# main.net
KiCad netlist of a schematic drawn in EAGLE
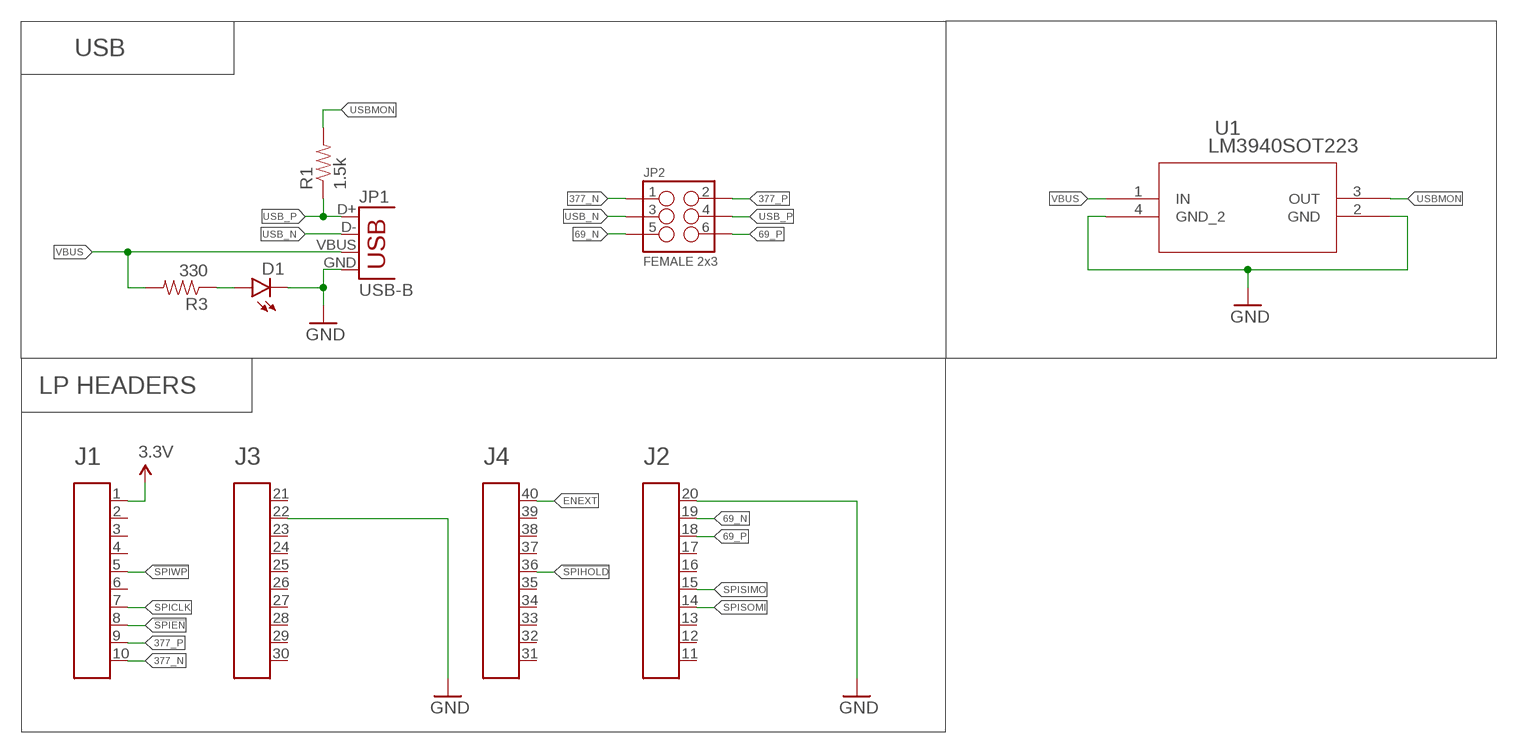
[diagram p0: schematic, sheet 1]

(export (version "E")
  (design (tool "Eeschema 10.0.6"))
  (components
    (comp (ref "A1")
      (value "HEADER4X10-BOOSTERPACK")
      (footprint "eagle-import:4X10-BOOSTERPACK")
      (libsource (lib "eagle-import") (part "HEADER4X10-BOOSTERPACK"))
    )
    (comp (ref "D1")
      (value "LED3MM")
      (footprint "eagle-import:LED3MM")
      (libsource (lib "eagle-import") (part "LED3MM"))
    )
    (comp (ref "JP1")
      (value "USB-B")
      (footprint "eagle-import:USB-B-PTH")
      (libsource (lib "eagle-import") (part "USBPTH"))
    )
    (comp (ref "JP2")
      (value "FEMALE 2x3")
      (footprint "eagle-import:2X3")
      (libsource (lib "eagle-import") (part "M03X2FEMALE"))
    )
    (comp (ref "R1")
      (value "1.5k")
      (footprint "eagle-import:AXIAL-0.3")
      (libsource (lib "eagle-import") (part "1KOHM-1/4W-5%(PTH)"))
    )
    (comp (ref "R3")
      (value "330")
      (footprint "eagle-import:AXIAL-0.3")
      (libsource (lib "eagle-import") (part "1KOHM-1/4W-5%(PTH)"))
    )
    (comp (ref "U1")
      (value "LM3940SOT223")
      (footprint "eagle-import:DCY")
      (libsource (lib "eagle-import") (part "LM3940SOT223"))
    )
  )
  (nets
    (net (code "1") (name "/~{SPIEN}") (class "Default")
      (node (ref "A1") (pin "8") (pinfunction "P$8_8") (pintype "bidirectional"))
    )
    (net (code "2") (name "/~{SPIHOLD}") (class "Default")
      (node (ref "A1") (pin "36") (pinfunction "P$36_36") (pintype "bidirectional"))
    )
    (net (code "3") (name "/~{SPIWP}") (class "Default")
      (node (ref "A1") (pin "5") (pinfunction "P$5_5") (pintype "bidirectional"))
    )
    (net (code "4") (name "3.3V") (class "Default")
      (node (ref "A1") (pin "1") (pinfunction "P$1_1") (pintype "bidirectional"))
    )
    (net (code "5") (name "69_N") (class "Default")
      (node (ref "A1") (pin "19") (pinfunction "P$19_19") (pintype "bidirectional"))
      (node (ref "JP2") (pin "5") (pinfunction "5_5") (pintype "bidirectional"))
    )
    (net (code "6") (name "69_P") (class "Default")
      (node (ref "A1") (pin "18") (pinfunction "P$18_18") (pintype "bidirectional"))
      (node (ref "JP2") (pin "6") (pinfunction "6_6") (pintype "bidirectional"))
    )
    (net (code "7") (name "377_N") (class "Default")
      (node (ref "A1") (pin "10") (pinfunction "P$10_10") (pintype "bidirectional"))
      (node (ref "JP2") (pin "1") (pinfunction "1_1") (pintype "bidirectional"))
    )
    (net (code "8") (name "377_P") (class "Default")
      (node (ref "A1") (pin "9") (pinfunction "P$9_9") (pintype "bidirectional"))
      (node (ref "JP2") (pin "2") (pinfunction "2_2") (pintype "bidirectional"))
    )
    (net (code "9") (name "ENEXT") (class "Default")
      (node (ref "A1") (pin "40") (pinfunction "P$40_40") (pintype "bidirectional"))
    )
    (net (code "10") (name "GND") (class "Default")
      (node (ref "A1") (pin "20") (pinfunction "P$20_20") (pintype "bidirectional"))
      (node (ref "A1") (pin "22") (pinfunction "P$22_22") (pintype "bidirectional"))
      (node (ref "D1") (pin "K") (pinfunction "C_K") (pintype "passive"))
      (node (ref "JP1") (pin "GND") (pinfunction "GND_GND") (pintype "bidirectional"))
      (node (ref "U1") (pin "2") (pinfunction "GND_2") (pintype "passive"))
      (node (ref "U1") (pin "4") (pinfunction "GND_2_4") (pintype "passive"))
    )
    (net (code "11") (name "Net-(R3-1)") (class "Default")
      (node (ref "D1") (pin "A") (pinfunction "A_A") (pintype "passive"))
      (node (ref "R3") (pin "P$1") (pinfunction "1_P$1") (pintype "passive"))
    )
    (net (code "12") (name "SPICLK") (class "Default")
      (node (ref "A1") (pin "7") (pinfunction "P$7_7") (pintype "bidirectional"))
    )
    (net (code "13") (name "SPISIMO") (class "Default")
      (node (ref "A1") (pin "15") (pinfunction "P$15_15") (pintype "bidirectional"))
    )
    (net (code "14") (name "SPISOMI") (class "Default")
      (node (ref "A1") (pin "14") (pinfunction "P$14_14") (pintype "bidirectional"))
    )
    (net (code "15") (name "USBMON") (class "Default")
      (node (ref "R1") (pin "P$2") (pinfunction "2_P$2") (pintype "passive"))
      (node (ref "U1") (pin "3") (pinfunction "OUT_3") (pintype "output"))
    )
    (net (code "16") (name "USB_N") (class "Default")
      (node (ref "JP1") (pin "D-") (pinfunction "D-_D-") (pintype "bidirectional"))
      (node (ref "JP2") (pin "3") (pinfunction "3_3") (pintype "bidirectional"))
    )
    (net (code "17") (name "USB_P") (class "Default")
      (node (ref "JP1") (pin "D+") (pinfunction "D+_D+") (pintype "bidirectional"))
      (node (ref "JP2") (pin "4") (pinfunction "4_4") (pintype "bidirectional"))
      (node (ref "R1") (pin "P$1") (pinfunction "1_P$1") (pintype "passive"))
    )
    (net (code "18") (name "VBUS") (class "Default")
      (node (ref "JP1") (pin "VBUS") (pinfunction "VBUS_VBUS") (pintype "bidirectional"))
      (node (ref "R3") (pin "P$2") (pinfunction "2_P$2") (pintype "passive"))
      (node (ref "U1") (pin "1") (pinfunction "IN_1") (pintype "input"))
    )
    (net (code "19") (name "unconnected-(A1-P$2-Pad2)") (class "Default")
      (node (ref "A1") (pin "2") (pinfunction "P$2_2") (pintype "bidirectional"))
    )
    (net (code "20") (name "unconnected-(A1-P$3-Pad3)") (class "Default")
      (node (ref "A1") (pin "3") (pinfunction "P$3_3") (pintype "bidirectional"))
    )
    (net (code "21") (name "unconnected-(A1-P$4-Pad4)") (class "Default")
      (node (ref "A1") (pin "4") (pinfunction "P$4_4") (pintype "bidirectional"))
    )
    (net (code "22") (name "unconnected-(A1-P$6-Pad6)") (class "Default")
      (node (ref "A1") (pin "6") (pinfunction "P$6_6") (pintype "bidirectional"))
    )
    (net (code "23") (name "unconnected-(A1-P$11-Pad11)") (class "Default")
      (node (ref "A1") (pin "11") (pinfunction "P$11_11") (pintype "bidirectional"))
    )
    (net (code "24") (name "unconnected-(A1-P$12-Pad12)") (class "Default")
      (node (ref "A1") (pin "12") (pinfunction "P$12_12") (pintype "bidirectional"))
    )
    (net (code "25") (name "unconnected-(A1-P$13-Pad13)") (class "Default")
      (node (ref "A1") (pin "13") (pinfunction "P$13_13") (pintype "bidirectional"))
    )
    (net (code "26") (name "unconnected-(A1-P$16-Pad16)") (class "Default")
      (node (ref "A1") (pin "16") (pinfunction "P$16_16") (pintype "bidirectional"))
    )
    (net (code "27") (name "unconnected-(A1-P$17-Pad17)") (class "Default")
      (node (ref "A1") (pin "17") (pinfunction "P$17_17") (pintype "bidirectional"))
    )
    (net (code "28") (name "unconnected-(A1-P$21-Pad21)") (class "Default")
      (node (ref "A1") (pin "21") (pinfunction "P$21_21") (pintype "bidirectional"))
    )
    (net (code "29") (name "unconnected-(A1-P$23-Pad23)") (class "Default")
      (node (ref "A1") (pin "23") (pinfunction "P$23_23") (pintype "bidirectional"))
    )
    (net (code "30") (name "unconnected-(A1-P$24-Pad24)") (class "Default")
      (node (ref "A1") (pin "24") (pinfunction "P$24_24") (pintype "bidirectional"))
    )
    (net (code "31") (name "unconnected-(A1-P$25-Pad25)") (class "Default")
      (node (ref "A1") (pin "25") (pinfunction "P$25_25") (pintype "bidirectional"))
    )
    (net (code "32") (name "unconnected-(A1-P$26-Pad26)") (class "Default")
      (node (ref "A1") (pin "26") (pinfunction "P$26_26") (pintype "bidirectional"))
    )
    (net (code "33") (name "unconnected-(A1-P$27-Pad27)") (class "Default")
      (node (ref "A1") (pin "27") (pinfunction "P$27_27") (pintype "bidirectional"))
    )
    (net (code "34") (name "unconnected-(A1-P$28-Pad28)") (class "Default")
      (node (ref "A1") (pin "28") (pinfunction "P$28_28") (pintype "bidirectional"))
    )
    (net (code "35") (name "unconnected-(A1-P$29-Pad29)") (class "Default")
      (node (ref "A1") (pin "29") (pinfunction "P$29_29") (pintype "bidirectional"))
    )
    (net (code "36") (name "unconnected-(A1-P$30-Pad30)") (class "Default")
      (node (ref "A1") (pin "30") (pinfunction "P$30_30") (pintype "bidirectional"))
    )
    (net (code "37") (name "unconnected-(A1-P$31-Pad31)") (class "Default")
      (node (ref "A1") (pin "31") (pinfunction "P$31_31") (pintype "bidirectional"))
    )
    (net (code "38") (name "unconnected-(A1-P$32-Pad32)") (class "Default")
      (node (ref "A1") (pin "32") (pinfunction "P$32_32") (pintype "bidirectional"))
    )
    (net (code "39") (name "unconnected-(A1-P$33-Pad33)") (class "Default")
      (node (ref "A1") (pin "33") (pinfunction "P$33_33") (pintype "bidirectional"))
    )
    (net (code "40") (name "unconnected-(A1-P$34-Pad34)") (class "Default")
      (node (ref "A1") (pin "34") (pinfunction "P$34_34") (pintype "bidirectional"))
    )
    (net (code "41") (name "unconnected-(A1-P$35-Pad35)") (class "Default")
      (node (ref "A1") (pin "35") (pinfunction "P$35_35") (pintype "bidirectional"))
    )
    (net (code "42") (name "unconnected-(A1-P$37-Pad37)") (class "Default")
      (node (ref "A1") (pin "37") (pinfunction "P$37_37") (pintype "bidirectional"))
    )
    (net (code "43") (name "unconnected-(A1-P$38-Pad38)") (class "Default")
      (node (ref "A1") (pin "38") (pinfunction "P$38_38") (pintype "bidirectional"))
    )
    (net (code "44") (name "unconnected-(A1-P$39-Pad39)") (class "Default")
      (node (ref "A1") (pin "39") (pinfunction "P$39_39") (pintype "bidirectional"))
    )
  )
)
